# item_2022_Frontend_02_V7.net
KiCad netlist of a schematic drawn in EAGLE
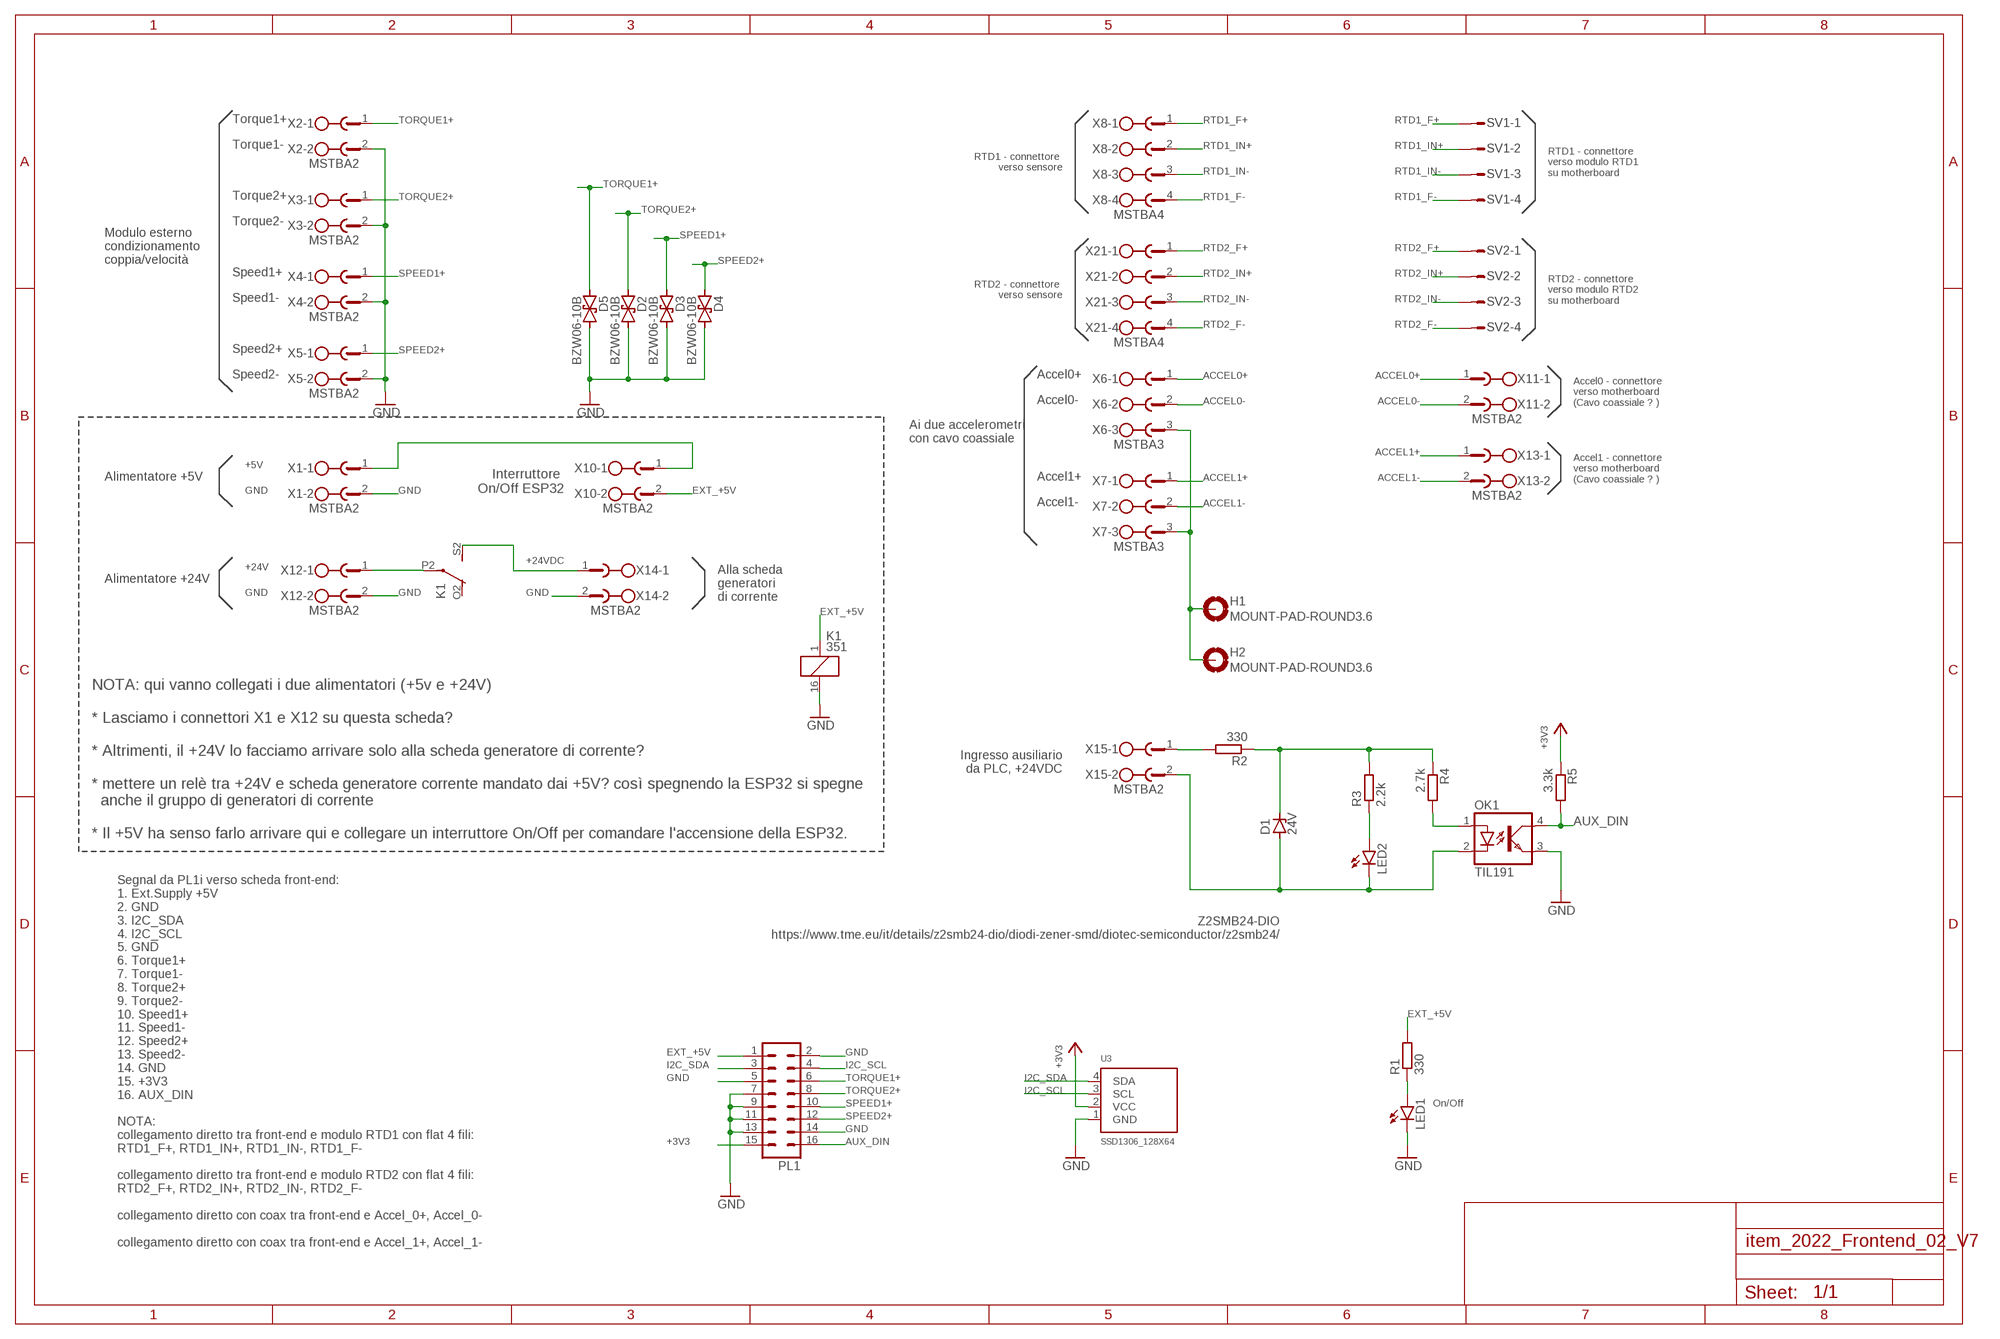
[diagram p0: schematic, sheet 1]

(export (version "E")
  (design (tool "Eeschema 10.0.6"))
  (components
    (comp (ref "D1")
      (value "24V")
      (footprint "eagle-import:DO35Z10")
      (libsource (lib "eagle-import") (part "ZENER-DIODEDO35Z10"))
    )
    (comp (ref "D2")
      (value "BZW06-10B")
      (footprint "eagle-import:F126Z12")
      (libsource (lib "eagle-import") (part "BZW04XXB"))
    )
    (comp (ref "D3")
      (value "BZW06-10B")
      (footprint "eagle-import:F126Z12")
      (libsource (lib "eagle-import") (part "BZW04XXB"))
    )
    (comp (ref "D4")
      (value "BZW06-10B")
      (footprint "eagle-import:F126Z12")
      (libsource (lib "eagle-import") (part "BZW04XXB"))
    )
    (comp (ref "D5")
      (value "BZW06-10B")
      (footprint "eagle-import:F126Z12")
      (libsource (lib "eagle-import") (part "BZW04XXB"))
    )
    (comp (ref "H1")
      (value "MOUNT-PAD-ROUND3.6")
      (footprint "eagle-import:3,6-PAD")
      (libsource (lib "eagle-import") (part "MOUNT-PAD-ROUND3.6"))
    )
    (comp (ref "H2")
      (value "MOUNT-PAD-ROUND3.6")
      (footprint "eagle-import:3,6-PAD")
      (libsource (lib "eagle-import") (part "MOUNT-PAD-ROUND3.6"))
    )
    (comp (ref "K1")
      (value "351")
      (footprint "eagle-import:351")
      (libsource (lib "eagle-import") (part "351"))
    )
    (comp (ref "LED1")
      (value "LED5MM")
      (footprint "eagle-import:LED5MM")
      (libsource (lib "eagle-import") (part "LED5MM"))
    )
    (comp (ref "LED2")
      (value "LED5MM")
      (footprint "eagle-import:LED5MM")
      (libsource (lib "eagle-import") (part "LED5MM"))
    )
    (comp (ref "OK1")
      (value "TIL191")
      (footprint "eagle-import:DIL04")
      (libsource (lib "eagle-import") (part "TIL191"))
    )
    (comp (ref "PL1")
      (value "16H")
      (footprint "eagle-import:16H")
      (libsource (lib "eagle-import") (part "16H"))
    )
    (comp (ref "R1")
      (value "330")
      (footprint "eagle-import:R0805")
      (libsource (lib "eagle-import") (part "R-EU_R0805"))
    )
    (comp (ref "R2")
      (value "330")
      (footprint "eagle-import:R0805")
      (libsource (lib "eagle-import") (part "R-EU_R0805"))
    )
    (comp (ref "R3")
      (value "2.2k")
      (footprint "eagle-import:R0805")
      (libsource (lib "eagle-import") (part "R-EU_R0805"))
    )
    (comp (ref "R4")
      (value "2.7k")
      (footprint "eagle-import:R0805")
      (libsource (lib "eagle-import") (part "R-EU_R0805"))
    )
    (comp (ref "R5")
      (value "3.3k")
      (footprint "eagle-import:R0805")
      (libsource (lib "eagle-import") (part "R-EU_R0805"))
    )
    (comp (ref "SV1")
      (value "S04P")
      (footprint "eagle-import:S04P")
      (libsource (lib "eagle-import") (part "S04P"))
    )
    (comp (ref "SV2")
      (value "S04P")
      (footprint "eagle-import:S04P")
      (libsource (lib "eagle-import") (part "S04P"))
    )
    (comp (ref "U3")
      (value "SSD1306_128X64")
      (footprint "eagle-import:128X64")
      (libsource (lib "eagle-import") (part "SSD1306_128X64"))
    )
    (comp (ref "X1")
      (value "MSTBA2")
      (footprint "eagle-import:MSTBA2")
      (fields (field (name "MF") "FARNELL") (field (name "MPN") "1757242"))
      (libsource (lib "eagle-import") (part "MSTBA2"))
    )
    (comp (ref "X2")
      (value "MSTBA2")
      (footprint "eagle-import:MSTBA2")
      (fields (field (name "MF") "FARNELL") (field (name "MPN") "1757242"))
      (libsource (lib "eagle-import") (part "MSTBA2"))
    )
    (comp (ref "X3")
      (value "MSTBA2")
      (footprint "eagle-import:MSTBA2")
      (fields (field (name "MF") "FARNELL") (field (name "MPN") "1757242"))
      (libsource (lib "eagle-import") (part "MSTBA2"))
    )
    (comp (ref "X4")
      (value "MSTBA2")
      (footprint "eagle-import:MSTBA2")
      (fields (field (name "MF") "FARNELL") (field (name "MPN") "1757242"))
      (libsource (lib "eagle-import") (part "MSTBA2"))
    )
    (comp (ref "X5")
      (value "MSTBA2")
      (footprint "eagle-import:MSTBA2")
      (fields (field (name "MF") "FARNELL") (field (name "MPN") "1757242"))
      (libsource (lib "eagle-import") (part "MSTBA2"))
    )
    (comp (ref "X6")
      (value "MSTBA3")
      (footprint "eagle-import:MSTBA3")
      (fields (field (name "MF") "FARNELL") (field (name "MPN") "1757255"))
      (libsource (lib "eagle-import") (part "MSTBA3"))
    )
    (comp (ref "X7")
      (value "MSTBA3")
      (footprint "eagle-import:MSTBA3")
      (fields (field (name "MF") "FARNELL") (field (name "MPN") "1757255"))
      (libsource (lib "eagle-import") (part "MSTBA3"))
    )
    (comp (ref "X8")
      (value "MSTBA4")
      (footprint "eagle-import:MSTBA4")
      (fields (field (name "MF") "FARNELL") (field (name "MPN") "1757268"))
      (libsource (lib "eagle-import") (part "MSTBA4"))
    )
    (comp (ref "X10")
      (value "MSTBA2")
      (footprint "eagle-import:MSTBA2")
      (fields (field (name "MF") "FARNELL") (field (name "MPN") "1757242"))
      (libsource (lib "eagle-import") (part "MSTBA2"))
    )
    (comp (ref "X11")
      (value "MSTBA2")
      (footprint "eagle-import:MSTBA2")
      (fields (field (name "MF") "FARNELL") (field (name "MPN") "1757242"))
      (libsource (lib "eagle-import") (part "MSTBA2"))
    )
    (comp (ref "X12")
      (value "MSTBA2")
      (footprint "eagle-import:MSTBA2")
      (fields (field (name "MF") "FARNELL") (field (name "MPN") "1757242"))
      (libsource (lib "eagle-import") (part "MSTBA2"))
    )
    (comp (ref "X13")
      (value "MSTBA2")
      (footprint "eagle-import:MSTBA2")
      (fields (field (name "MF") "FARNELL") (field (name "MPN") "1757242"))
      (libsource (lib "eagle-import") (part "MSTBA2"))
    )
    (comp (ref "X14")
      (value "MSTBA2")
      (footprint "eagle-import:MSTBA2")
      (fields (field (name "MF") "FARNELL") (field (name "MPN") "1757242"))
      (libsource (lib "eagle-import") (part "MSTBA2"))
    )
    (comp (ref "X15")
      (value "MSTBA2")
      (footprint "eagle-import:MSTBA2")
      (fields (field (name "MF") "FARNELL") (field (name "MPN") "1757242"))
      (libsource (lib "eagle-import") (part "MSTBA2"))
    )
    (comp (ref "X21")
      (value "MSTBA4")
      (footprint "eagle-import:MSTBA4")
      (fields (field (name "MF") "FARNELL") (field (name "MPN") "1757268"))
      (libsource (lib "eagle-import") (part "MSTBA4"))
    )
  )
  (nets
    (net (code "1") (name "+3V3") (class "Default")
      (node (ref "PL1") (pin "15") (pinfunction "15_15") (pintype "passive"))
      (node (ref "R5") (pin "1") (pinfunction "1_1") (pintype "passive"))
      (node (ref "U3") (pin "2") (pinfunction "VCC_2") (pintype "power_in"))
    )
    (net (code "2") (name "/+24VDC") (class "Default")
      (node (ref "K1") (pin "S2") (pinfunction "S_S2") (pintype "passive"))
      (node (ref "X14") (pin "1") (pinfunction "1_1") (pintype "passive"))
    )
    (net (code "3") (name "/ACCEL0+") (class "Default")
      (node (ref "X11") (pin "1") (pinfunction "1_1") (pintype "passive"))
      (node (ref "X6") (pin "1") (pinfunction "1_1") (pintype "passive"))
    )
    (net (code "4") (name "/ACCEL0-") (class "Default")
      (node (ref "X11") (pin "2") (pinfunction "1_2") (pintype "passive"))
      (node (ref "X6") (pin "2") (pinfunction "1_2") (pintype "passive"))
    )
    (net (code "5") (name "/ACCEL1+") (class "Default")
      (node (ref "X13") (pin "1") (pinfunction "1_1") (pintype "passive"))
      (node (ref "X7") (pin "1") (pinfunction "1_1") (pintype "passive"))
    )
    (net (code "6") (name "/ACCEL1-") (class "Default")
      (node (ref "X13") (pin "2") (pinfunction "1_2") (pintype "passive"))
      (node (ref "X7") (pin "2") (pinfunction "1_2") (pintype "passive"))
    )
    (net (code "7") (name "/AUX_DIN") (class "Default")
      (node (ref "OK1") (pin "4") (pinfunction "COL_4") (pintype "passive"))
      (node (ref "PL1") (pin "16") (pinfunction "16_16") (pintype "passive"))
      (node (ref "R5") (pin "2") (pinfunction "2_2") (pintype "passive"))
    )
    (net (code "8") (name "/EXT_+5V") (class "Default")
      (node (ref "K1") (pin "1") (pinfunction "1_1") (pintype "passive"))
      (node (ref "PL1") (pin "1") (pinfunction "1_1") (pintype "passive"))
      (node (ref "R1") (pin "2") (pinfunction "2_2") (pintype "passive"))
      (node (ref "X10") (pin "2") (pinfunction "1_2") (pintype "passive"))
    )
    (net (code "9") (name "/I2C_SCL") (class "Default")
      (node (ref "PL1") (pin "4") (pinfunction "4_4") (pintype "passive"))
      (node (ref "U3") (pin "3") (pinfunction "SCL_3") (pintype "bidirectional"))
    )
    (net (code "10") (name "/I2C_SDA") (class "Default")
      (node (ref "PL1") (pin "3") (pinfunction "3_3") (pintype "passive"))
      (node (ref "U3") (pin "4") (pinfunction "SDA_4") (pintype "bidirectional"))
    )
    (net (code "11") (name "/RTD1_F+") (class "Default")
      (node (ref "SV1") (pin "1") (pinfunction "S_1") (pintype "passive"))
      (node (ref "X8") (pin "1") (pinfunction "1_1") (pintype "passive"))
    )
    (net (code "12") (name "/RTD1_F-") (class "Default")
      (node (ref "SV1") (pin "4") (pinfunction "S_4") (pintype "passive"))
      (node (ref "X8") (pin "4") (pinfunction "1_4") (pintype "passive"))
    )
    (net (code "13") (name "/RTD1_IN+") (class "Default")
      (node (ref "SV1") (pin "2") (pinfunction "S_2") (pintype "passive"))
      (node (ref "X8") (pin "2") (pinfunction "1_2") (pintype "passive"))
    )
    (net (code "14") (name "/RTD1_IN-") (class "Default")
      (node (ref "SV1") (pin "3") (pinfunction "S_3") (pintype "passive"))
      (node (ref "X8") (pin "3") (pinfunction "1_3") (pintype "passive"))
    )
    (net (code "15") (name "/RTD2_F+") (class "Default")
      (node (ref "SV2") (pin "1") (pinfunction "S_1") (pintype "passive"))
      (node (ref "X21") (pin "1") (pinfunction "1_1") (pintype "passive"))
    )
    (net (code "16") (name "/RTD2_F-") (class "Default")
      (node (ref "SV2") (pin "4") (pinfunction "S_4") (pintype "passive"))
      (node (ref "X21") (pin "4") (pinfunction "1_4") (pintype "passive"))
    )
    (net (code "17") (name "/RTD2_IN+") (class "Default")
      (node (ref "SV2") (pin "2") (pinfunction "S_2") (pintype "passive"))
      (node (ref "X21") (pin "2") (pinfunction "1_2") (pintype "passive"))
    )
    (net (code "18") (name "/RTD2_IN-") (class "Default")
      (node (ref "SV2") (pin "3") (pinfunction "S_3") (pintype "passive"))
      (node (ref "X21") (pin "3") (pinfunction "1_3") (pintype "passive"))
    )
    (net (code "19") (name "/SPEED1+") (class "Default")
      (node (ref "D3") (pin "A") (pinfunction "1_A") (pintype "passive"))
      (node (ref "PL1") (pin "10") (pinfunction "10_10") (pintype "passive"))
      (node (ref "X4") (pin "1") (pinfunction "1_1") (pintype "passive"))
    )
    (net (code "20") (name "/SPEED2+") (class "Default")
      (node (ref "D4") (pin "A") (pinfunction "1_A") (pintype "passive"))
      (node (ref "PL1") (pin "12") (pinfunction "12_12") (pintype "passive"))
      (node (ref "X5") (pin "1") (pinfunction "1_1") (pintype "passive"))
    )
    (net (code "21") (name "/TORQUE1+") (class "Default")
      (node (ref "D5") (pin "A") (pinfunction "1_A") (pintype "passive"))
      (node (ref "PL1") (pin "6") (pinfunction "6_6") (pintype "passive"))
      (node (ref "X2") (pin "1") (pinfunction "1_1") (pintype "passive"))
    )
    (net (code "22") (name "/TORQUE2+") (class "Default")
      (node (ref "D2") (pin "A") (pinfunction "1_A") (pintype "passive"))
      (node (ref "PL1") (pin "8") (pinfunction "8_8") (pintype "passive"))
      (node (ref "X3") (pin "1") (pinfunction "1_1") (pintype "passive"))
    )
    (net (code "23") (name "GND") (class "Default")
      (node (ref "D2") (pin "C") (pinfunction "2_C") (pintype "passive"))
      (node (ref "D3") (pin "C") (pinfunction "2_C") (pintype "passive"))
      (node (ref "D4") (pin "C") (pinfunction "2_C") (pintype "passive"))
      (node (ref "D5") (pin "C") (pinfunction "2_C") (pintype "passive"))
      (node (ref "K1") (pin "16") (pinfunction "2_16") (pintype "passive"))
      (node (ref "LED1") (pin "K") (pinfunction "C_K") (pintype "passive"))
      (node (ref "OK1") (pin "3") (pinfunction "EMIT_3") (pintype "passive"))
      (node (ref "PL1") (pin "11") (pinfunction "11_11") (pintype "passive"))
      (node (ref "PL1") (pin "13") (pinfunction "13_13") (pintype "passive"))
      (node (ref "PL1") (pin "14") (pinfunction "14_14") (pintype "passive"))
      (node (ref "PL1") (pin "2") (pinfunction "2_2") (pintype "passive"))
      (node (ref "PL1") (pin "5") (pinfunction "5_5") (pintype "passive"))
      (node (ref "PL1") (pin "7") (pinfunction "7_7") (pintype "passive"))
      (node (ref "PL1") (pin "9") (pinfunction "9_9") (pintype "passive"))
      (node (ref "U3") (pin "1") (pinfunction "GND_1") (pintype "power_in"))
      (node (ref "X1") (pin "2") (pinfunction "1_2") (pintype "passive"))
      (node (ref "X12") (pin "2") (pinfunction "1_2") (pintype "passive"))
      (node (ref "X14") (pin "2") (pinfunction "1_2") (pintype "passive"))
      (node (ref "X2") (pin "2") (pinfunction "1_2") (pintype "passive"))
      (node (ref "X3") (pin "2") (pinfunction "1_2") (pintype "passive"))
      (node (ref "X4") (pin "2") (pinfunction "1_2") (pintype "passive"))
      (node (ref "X5") (pin "2") (pinfunction "1_2") (pintype "passive"))
    )
    (net (code "24") (name "Net-(D1-PadC)") (class "Default")
      (node (ref "D1") (pin "C") (pinfunction "C_C") (pintype "passive"))
      (node (ref "R2") (pin "1") (pinfunction "1_1") (pintype "passive"))
      (node (ref "R3") (pin "2") (pinfunction "2_2") (pintype "passive"))
      (node (ref "R4") (pin "1") (pinfunction "1_1") (pintype "passive"))
    )
    (net (code "25") (name "Net-(H1-MOUNT)") (class "Default")
      (node (ref "H1") (pin "B3,6") (pinfunction "MOUNT_B3,6") (pintype "passive"))
      (node (ref "H2") (pin "B3,6") (pinfunction "MOUNT_B3,6") (pintype "passive"))
      (node (ref "X6") (pin "3") (pinfunction "1_3") (pintype "passive"))
      (node (ref "X7") (pin "3") (pinfunction "1_3") (pintype "passive"))
    )
    (net (code "26") (name "Net-(K1C-P)") (class "Default")
      (node (ref "K1") (pin "P2") (pinfunction "P_P2") (pintype "passive"))
      (node (ref "X12") (pin "1") (pinfunction "1_1") (pintype "passive"))
    )
    (net (code "27") (name "Net-(LED1-PadA)") (class "Default")
      (node (ref "LED1") (pin "A") (pinfunction "A_A") (pintype "passive"))
      (node (ref "R1") (pin "1") (pinfunction "1_1") (pintype "passive"))
    )
    (net (code "28") (name "Net-(LED2-C)") (class "Default")
      (node (ref "D1") (pin "A") (pinfunction "A_A") (pintype "passive"))
      (node (ref "LED2") (pin "K") (pinfunction "C_K") (pintype "passive"))
      (node (ref "OK1") (pin "2") (pinfunction "C_2") (pintype "passive"))
      (node (ref "X15") (pin "2") (pinfunction "1_2") (pintype "passive"))
    )
    (net (code "29") (name "Net-(LED2-PadA)") (class "Default")
      (node (ref "LED2") (pin "A") (pinfunction "A_A") (pintype "passive"))
      (node (ref "R3") (pin "1") (pinfunction "1_1") (pintype "passive"))
    )
    (net (code "30") (name "Net-(OK1-A)") (class "Default")
      (node (ref "OK1") (pin "1") (pinfunction "A_1") (pintype "passive"))
      (node (ref "R4") (pin "2") (pinfunction "2_2") (pintype "passive"))
    )
    (net (code "31") (name "Net-(R2-Pad2)") (class "Default")
      (node (ref "R2") (pin "2") (pinfunction "2_2") (pintype "passive"))
      (node (ref "X15") (pin "1") (pinfunction "1_1") (pintype "passive"))
    )
    (net (code "32") (name "Net-(X1-Pad1)") (class "Default")
      (node (ref "X1") (pin "1") (pinfunction "1_1") (pintype "passive"))
      (node (ref "X10") (pin "1") (pinfunction "1_1") (pintype "passive"))
    )
    (net (code "33") (name "unconnected-(K1C-O-PadO2)") (class "Default")
      (node (ref "K1") (pin "O2") (pinfunction "O_O2") (pintype "passive"))
    )
  )
)
